# comms_sys_schematic_V1.net
KiCad netlist of a schematic drawn in EAGLE
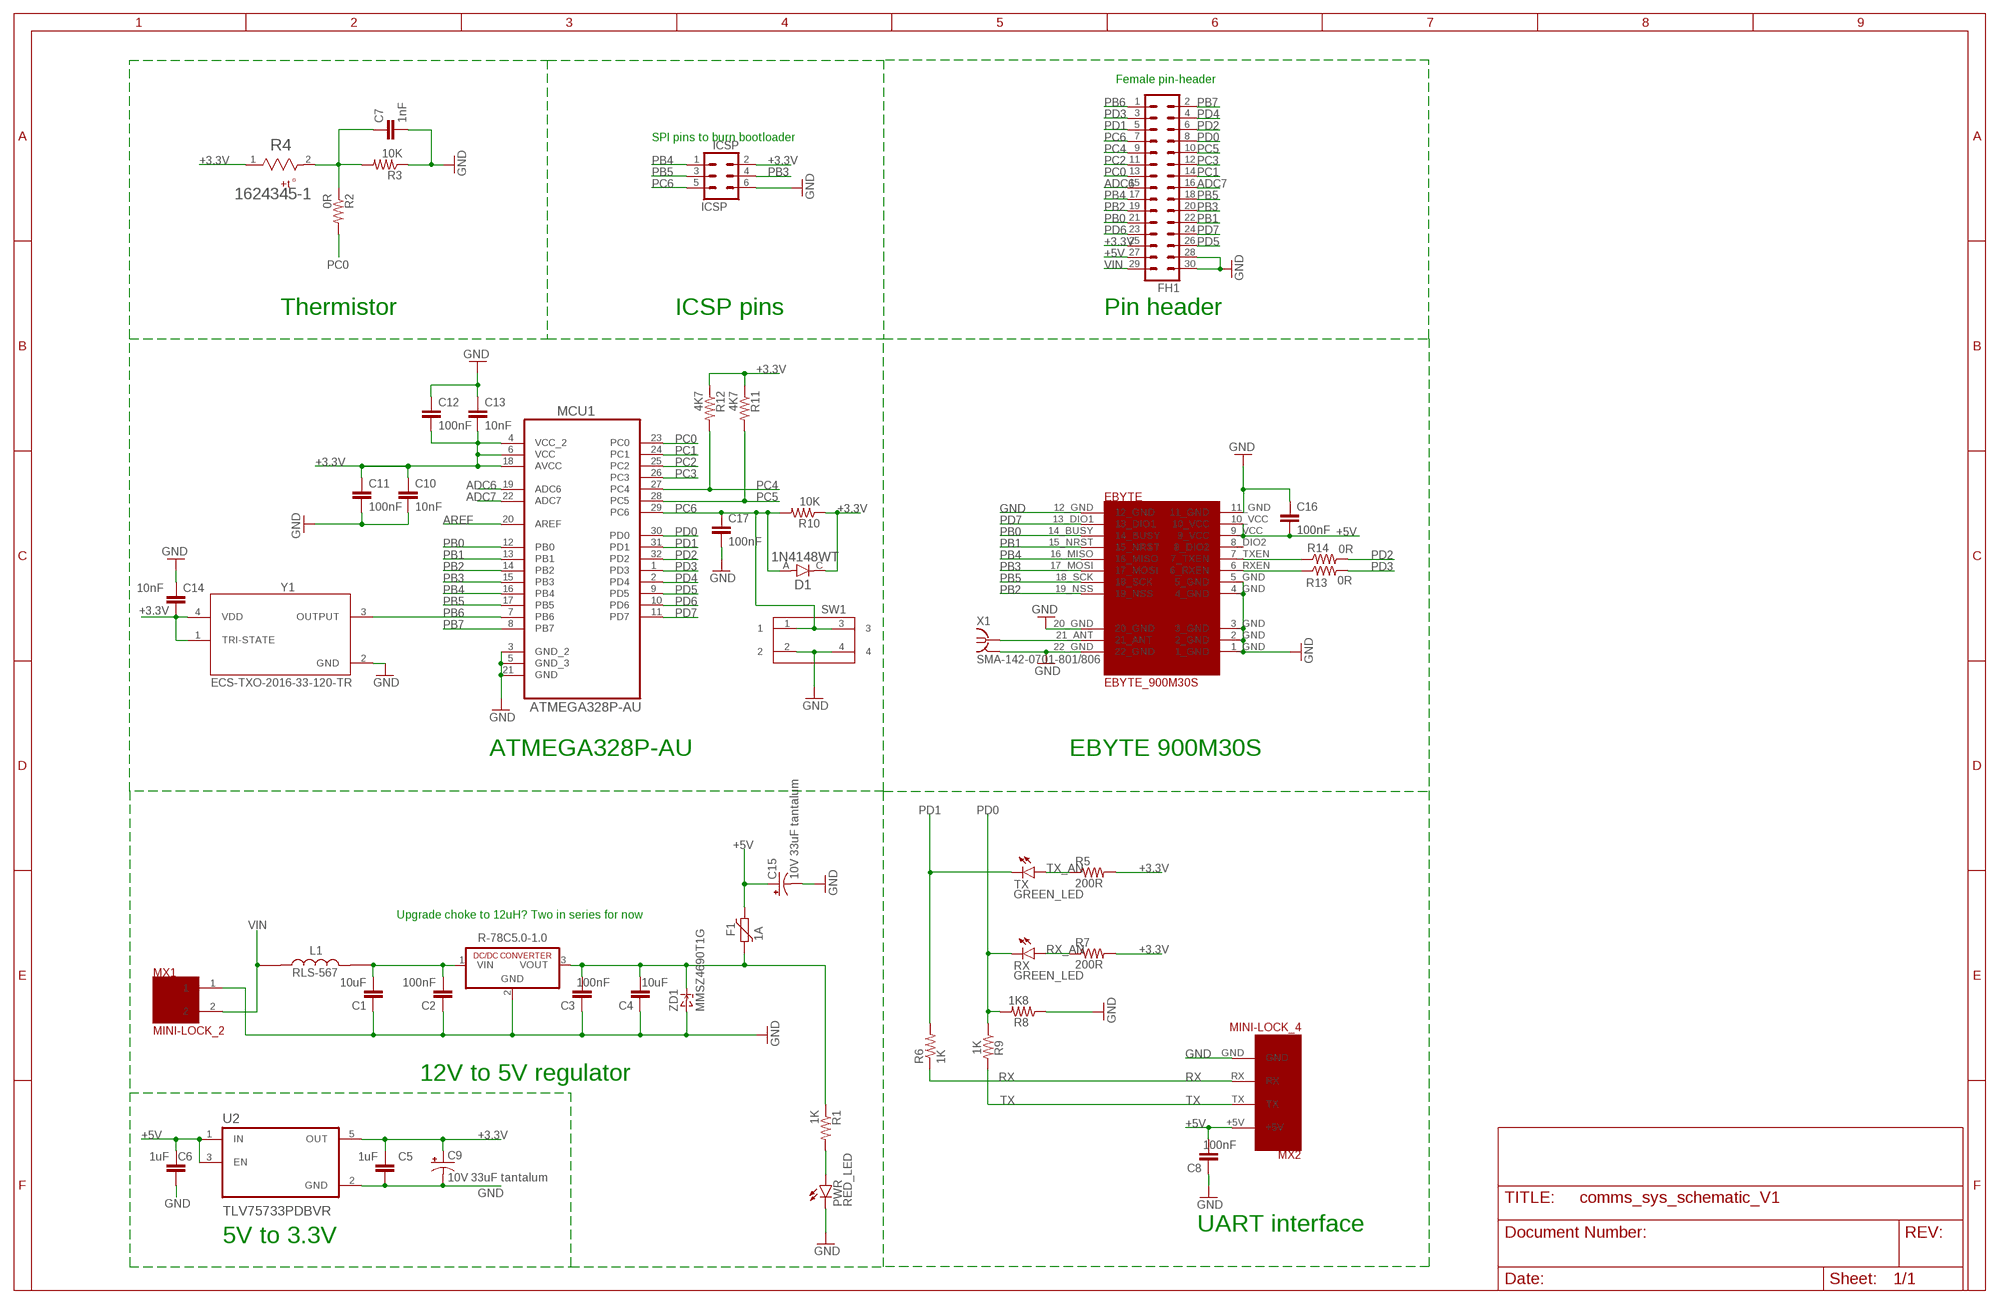
[diagram p0: schematic, sheet 1]

(export (version "E")
  (design (tool "Eeschema 10.0.6"))
  (components
    (comp (ref "C1")
      (value "10uF")
      (footprint "eagle-import:C0805")
      (libsource (lib "eagle-import") (part "C-EUC0805"))
    )
    (comp (ref "C2")
      (value "100nF")
      (footprint "eagle-import:C0805")
      (libsource (lib "eagle-import") (part "C-EUC0805"))
    )
    (comp (ref "C3")
      (value "100nF")
      (footprint "eagle-import:C0805")
      (libsource (lib "eagle-import") (part "C-EUC0805"))
    )
    (comp (ref "C4")
      (value "10uF")
      (footprint "eagle-import:C0805")
      (libsource (lib "eagle-import") (part "C-EUC0805"))
    )
    (comp (ref "C5")
      (value "1uF")
      (footprint "eagle-import:C0805")
      (libsource (lib "eagle-import") (part "C-EUC0805"))
    )
    (comp (ref "C6")
      (value "1uF")
      (footprint "eagle-import:C0805")
      (libsource (lib "eagle-import") (part "C-EUC0805"))
    )
    (comp (ref "C7")
      (value "1nF")
      (footprint "eagle-import:C0805")
      (libsource (lib "eagle-import") (part "C-EUC0805"))
    )
    (comp (ref "C8")
      (value "100nF")
      (footprint "eagle-import:C0805")
      (libsource (lib "eagle-import") (part "C-EUC0805"))
    )
    (comp (ref "C9")
      (value "10V 33uF tantalum")
      (footprint "eagle-import:CT3216")
      (libsource (lib "eagle-import") (part "CPOL-USCT3216"))
    )
    (comp (ref "C10")
      (value "10nF")
      (footprint "eagle-import:C0805")
      (libsource (lib "eagle-import") (part "C-EUC0805"))
    )
    (comp (ref "C11")
      (value "100nF")
      (footprint "eagle-import:C0805")
      (libsource (lib "eagle-import") (part "C-EUC0805"))
    )
    (comp (ref "C12")
      (value "100nF")
      (footprint "eagle-import:C0805")
      (libsource (lib "eagle-import") (part "C-EUC0805"))
    )
    (comp (ref "C13")
      (value "10nF")
      (footprint "eagle-import:C0805")
      (libsource (lib "eagle-import") (part "C-EUC0805"))
    )
    (comp (ref "C14")
      (value "10nF")
      (footprint "eagle-import:C0805")
      (libsource (lib "eagle-import") (part "C-EUC0805"))
    )
    (comp (ref "C15")
      (value "10V 33uF tantalum")
      (footprint "eagle-import:CT3216")
      (libsource (lib "eagle-import") (part "CPOL-USCT3216"))
    )
    (comp (ref "C16")
      (value "100nF")
      (footprint "eagle-import:C0805")
      (libsource (lib "eagle-import") (part "C-EUC0805"))
    )
    (comp (ref "C17")
      (value "100nF")
      (footprint "eagle-import:C0805")
      (libsource (lib "eagle-import") (part "C-EUC0805"))
    )
    (comp (ref "D1")
      (value "1N4148WT")
      (footprint "eagle-import:SODFL1608X70N")
      (fields (field (name "DIGI-KEY_PART_NUMBER") "1N4148WTCT-ND") (field (name "MF") "ON Semiconductor"))
      (libsource (lib "eagle-import") (part "1N4148WT"))
    )
    (comp (ref "EBYTE")
      (value "EBYTE_900M30S")
      (footprint "eagle-import:EBYTE_SX1262_900M30S_FOOTPRINT")
      (libsource (lib "eagle-import") (part "EBYTE_SX1262_900M30S"))
    )
    (comp (ref "F1")
      (value "1A")
      (footprint "eagle-import:PTC0805")
      (libsource (lib "eagle-import") (part "FUSE_PTC-0805"))
    )
    (comp (ref "FH1")
      (value "MA15-2")
      (footprint "eagle-import:MA15-2")
      (libsource (lib "eagle-import") (part "MA15-2"))
    )
    (comp (ref "ICSP")
      (value "ICSP")
      (footprint "eagle-import:MA03-2")
      (libsource (lib "eagle-import") (part "MA03-2"))
    )
    (comp (ref "L1")
      (value "RLS-567")
      (footprint "eagle-import:IND_RLS-567")
      (fields (field (name "MF") "Recom Power"))
      (libsource (lib "eagle-import") (part "RLS-567"))
    )
    (comp (ref "MCU1")
      (value "ATMEGA328P-AU")
      (footprint "eagle-import:QFP80P900X900X120-32N")
      (libsource (lib "eagle-import") (part "ATMEGA328P-AU"))
    )
    (comp (ref "MX1")
      (value "MINI-LOCK_2")
      (footprint "eagle-import:MINI-LOCK_2")
      (libsource (lib "eagle-import") (part "MINI-LOCK_2"))
    )
    (comp (ref "MX2")
      (value "MINI-LOCK_4")
      (footprint "eagle-import:MINI-LOCK_4")
      (libsource (lib "eagle-import") (part "MINI-LOCK_4"))
    )
    (comp (ref "PWR")
      (value "RED_LED")
      (footprint "eagle-import:CHIP-LED0805")
      (libsource (lib "eagle-import") (part "LEDCHIP-LED0805"))
    )
    (comp (ref "R1")
      (value "1K")
      (footprint "eagle-import:R0805")
      (libsource (lib "eagle-import") (part "R-US_R0805"))
    )
    (comp (ref "R2")
      (value "0R")
      (footprint "eagle-import:R0805")
      (libsource (lib "eagle-import") (part "R-US_R0805"))
    )
    (comp (ref "R3")
      (value "10K")
      (footprint "eagle-import:R0805")
      (libsource (lib "eagle-import") (part "R-US_R0805"))
    )
    (comp (ref "R4")
      (value "1624345-1")
      (footprint "eagle-import:THRMC2012X50N")
      (fields
        (field (name "DIGI-KEY_PART_NUMBER") "A106104CT-ND")
        (field (name "MF") "TE Connectivity")
        (field (name "MP") "NTC0805J10K")
      )
      (libsource (lib "eagle-import") (part "1624345-1"))
    )
    (comp (ref "R5")
      (value "200R")
      (footprint "eagle-import:R0805")
      (libsource (lib "eagle-import") (part "R-US_R0805"))
    )
    (comp (ref "R6")
      (value "1K")
      (footprint "eagle-import:R0805")
      (libsource (lib "eagle-import") (part "R-US_R0805"))
    )
    (comp (ref "R7")
      (value "200R")
      (footprint "eagle-import:R0805")
      (libsource (lib "eagle-import") (part "R-US_R0805"))
    )
    (comp (ref "R8")
      (value "1K8")
      (footprint "eagle-import:R0805")
      (libsource (lib "eagle-import") (part "R-US_R0805"))
    )
    (comp (ref "R9")
      (value "1K")
      (footprint "eagle-import:R0805")
      (libsource (lib "eagle-import") (part "R-US_R0805"))
    )
    (comp (ref "R10")
      (value "10K")
      (footprint "eagle-import:R0805")
      (libsource (lib "eagle-import") (part "R-US_R0805"))
    )
    (comp (ref "R11")
      (value "4K7")
      (footprint "eagle-import:R0805")
      (libsource (lib "eagle-import") (part "R-US_R0805"))
    )
    (comp (ref "R12")
      (value "4K7")
      (footprint "eagle-import:R0805")
      (libsource (lib "eagle-import") (part "R-US_R0805"))
    )
    (comp (ref "R13")
      (value "0R")
      (footprint "eagle-import:R0805")
      (libsource (lib "eagle-import") (part "R-US_R0805"))
    )
    (comp (ref "R14")
      (value "0R")
      (footprint "eagle-import:R0805")
      (libsource (lib "eagle-import") (part "R-US_R0805"))
    )
    (comp (ref "RX")
      (value "GREEN_LED")
      (footprint "eagle-import:CHIP-LED0805")
      (libsource (lib "eagle-import") (part "LEDCHIP-LED0805"))
    )
    (comp (ref "SW1")
      (value "430152043826")
      (footprint "eagle-import:430152043826")
      (libsource (lib "eagle-import") (part "430152043826"))
    )
    (comp (ref "TX")
      (value "GREEN_LED")
      (footprint "eagle-import:CHIP-LED0805")
      (libsource (lib "eagle-import") (part "LEDCHIP-LED0805"))
    )
    (comp (ref "U1")
      (value "R-78C5.0-1.0")
      (footprint "eagle-import:SIP3")
      (libsource (lib "eagle-import") (part "R-78C-1.05.0"))
    )
    (comp (ref "U2")
      (value "TLV75733PDBVR")
      (footprint "eagle-import:SOT95P280X145-5N")
      (fields (field (name "DIGI-KEY_PART_NUMBER") "296-50414-1-ND") (field (name "MF") "Texas Instruments"))
      (libsource (lib "eagle-import") (part "TLV75733PDBVR"))
    )
    (comp (ref "X1")
      (value "SMA-142-0701-801/806")
      (footprint "eagle-import:J502-ND-142-0701-801_806")
      (fields (field (name "MF") "JOHNSON COMPONENTS") (field (name "MPN") "142-0701-801"))
      (libsource (lib "eagle-import") (part "SMA-142-0701-801/806"))
    )
    (comp (ref "Y1")
      (value "ECS-TXO-2016-33-120-TR")
      (footprint "eagle-import:OSC_ECS-TXO-2016-33-120-TR")
      (fields (field (name "DIGI-KEY_PART_NUMBER") "XC3160CT-ND") (field (name "MF") "ECS Inc."))
      (libsource (lib "eagle-import") (part "ECS-TXO-2016-33-120-TR"))
    )
    (comp (ref "ZD1")
      (value "MMSZ4690T1G")
      (footprint "eagle-import:SOD-123")
      (libsource (lib "eagle-import") (part "ZENERSOD-123"))
    )
  )
  (nets
    (net (code "1") (name "/+3.3V") (class "Default")
      (node (ref "C10") (pin "1") (pinfunction "1_1") (pintype "passive"))
      (node (ref "C11") (pin "1") (pinfunction "1_1") (pintype "passive"))
      (node (ref "C12") (pin "2") (pinfunction "2_2") (pintype "passive"))
      (node (ref "C13") (pin "2") (pinfunction "2_2") (pintype "passive"))
      (node (ref "C14") (pin "2") (pinfunction "2_2") (pintype "passive"))
      (node (ref "C5") (pin "2") (pinfunction "2_2") (pintype "passive"))
      (node (ref "C9") (pin "+") (pinfunction "+_+") (pintype "passive"))
      (node (ref "D1") (pin "C") (pinfunction "C_C") (pintype "passive"))
      (node (ref "FH1") (pin "25") (pinfunction "29_25") (pintype "passive"))
      (node (ref "ICSP") (pin "2") (pinfunction "2_2") (pintype "passive"))
      (node (ref "MCU1") (pin "18") (pinfunction "AVCC_18") (pintype "power_in"))
      (node (ref "MCU1") (pin "4") (pinfunction "VCC_2_4") (pintype "power_in"))
      (node (ref "MCU1") (pin "6") (pinfunction "VCC_6") (pintype "power_in"))
      (node (ref "R10") (pin "1") (pinfunction "1_1") (pintype "passive"))
      (node (ref "R11") (pin "1") (pinfunction "1_1") (pintype "passive"))
      (node (ref "R12") (pin "1") (pinfunction "1_1") (pintype "passive"))
      (node (ref "R4") (pin "1") (pinfunction "1_1") (pintype "passive"))
      (node (ref "R5") (pin "2") (pinfunction "2_2") (pintype "passive"))
      (node (ref "R7") (pin "2") (pinfunction "2_2") (pintype "passive"))
      (node (ref "U2") (pin "5") (pinfunction "OUT_5") (pintype "output"))
      (node (ref "Y1") (pin "1") (pinfunction "TRI-STATE_1") (pintype "input"))
      (node (ref "Y1") (pin "4") (pinfunction "VDD_4") (pintype "input"))
    )
    (net (code "2") (name "/+5V") (class "Default")
      (node (ref "C15") (pin "+") (pinfunction "+_+") (pintype "passive"))
      (node (ref "C16") (pin "2") (pinfunction "2_2") (pintype "passive"))
      (node (ref "C6") (pin "2") (pinfunction "2_2") (pintype "passive"))
      (node (ref "C8") (pin "2") (pinfunction "2_2") (pintype "passive"))
      (node (ref "EBYTE") (pin "10_VCC") (pinfunction "10_VCC_10_VCC") (pintype "power_in"))
      (node (ref "EBYTE") (pin "9_VCC") (pinfunction "9_VCC_9_VCC") (pintype "power_in"))
      (node (ref "F1") (pin "2") (pinfunction "2_2") (pintype "passive"))
      (node (ref "FH1") (pin "27") (pinfunction "31_27") (pintype "passive"))
      (node (ref "MX2") (pin "+5V") (pinfunction "+5V_+5V") (pintype "bidirectional"))
      (node (ref "U2") (pin "1") (pinfunction "IN_1") (pintype "input"))
      (node (ref "U2") (pin "3") (pinfunction "EN_3") (pintype "bidirectional"))
    )
    (net (code "3") (name "/ADC6") (class "Default")
      (node (ref "FH1") (pin "15") (pinfunction "19_15") (pintype "passive"))
      (node (ref "MCU1") (pin "19") (pinfunction "ADC6_19") (pintype "input"))
    )
    (net (code "4") (name "/ADC7") (class "Default")
      (node (ref "FH1") (pin "16") (pinfunction "20_16") (pintype "passive"))
      (node (ref "MCU1") (pin "22") (pinfunction "ADC7_22") (pintype "input"))
    )
    (net (code "5") (name "/AREF") (class "Default")
      (node (ref "MCU1") (pin "20") (pinfunction "AREF_20") (pintype "input"))
    )
    (net (code "6") (name "/PB0") (class "Default")
      (node (ref "EBYTE") (pin "14_BUSY") (pinfunction "14_BUSY_14_BUSY") (pintype "bidirectional"))
      (node (ref "FH1") (pin "21") (pinfunction "25_21") (pintype "passive"))
      (node (ref "MCU1") (pin "12") (pinfunction "PB0_12") (pintype "bidirectional"))
    )
    (net (code "7") (name "/PB1") (class "Default")
      (node (ref "EBYTE") (pin "15_NRST") (pinfunction "15_NRST_15_NRST") (pintype "bidirectional"))
      (node (ref "FH1") (pin "22") (pinfunction "26_22") (pintype "passive"))
      (node (ref "MCU1") (pin "13") (pinfunction "PB1_13") (pintype "bidirectional"))
    )
    (net (code "8") (name "/PB2") (class "Default")
      (node (ref "EBYTE") (pin "19_NSS") (pinfunction "19_NSS_19_NSS") (pintype "bidirectional"))
      (node (ref "FH1") (pin "19") (pinfunction "23_19") (pintype "passive"))
      (node (ref "MCU1") (pin "14") (pinfunction "PB2_14") (pintype "bidirectional"))
    )
    (net (code "9") (name "/PB3") (class "Default")
      (node (ref "EBYTE") (pin "17_MOSI") (pinfunction "17_MOSI_17_MOSI") (pintype "bidirectional"))
      (node (ref "FH1") (pin "20") (pinfunction "24_20") (pintype "passive"))
      (node (ref "ICSP") (pin "4") (pinfunction "4_4") (pintype "passive"))
      (node (ref "MCU1") (pin "15") (pinfunction "PB3_15") (pintype "bidirectional"))
    )
    (net (code "10") (name "/PB4") (class "Default")
      (node (ref "EBYTE") (pin "16_MISO") (pinfunction "16_MISO_16_MISO") (pintype "bidirectional"))
      (node (ref "FH1") (pin "17") (pinfunction "21_17") (pintype "passive"))
      (node (ref "ICSP") (pin "1") (pinfunction "1_1") (pintype "passive"))
      (node (ref "MCU1") (pin "16") (pinfunction "PB4_16") (pintype "bidirectional"))
    )
    (net (code "11") (name "/PB5") (class "Default")
      (node (ref "EBYTE") (pin "18_SCK") (pinfunction "18_SCK_18_SCK") (pintype "bidirectional"))
      (node (ref "FH1") (pin "18") (pinfunction "22_18") (pintype "passive"))
      (node (ref "ICSP") (pin "3") (pinfunction "3_3") (pintype "passive"))
      (node (ref "MCU1") (pin "17") (pinfunction "PB5_17") (pintype "bidirectional"))
    )
    (net (code "12") (name "/PB6") (class "Default")
      (node (ref "FH1") (pin "1") (pinfunction "5_1") (pintype "passive"))
      (node (ref "MCU1") (pin "7") (pinfunction "PB6_7") (pintype "bidirectional"))
      (node (ref "Y1") (pin "3") (pinfunction "OUTPUT_3") (pintype "output"))
    )
    (net (code "13") (name "/PB7") (class "Default")
      (node (ref "FH1") (pin "2") (pinfunction "6_2") (pintype "passive"))
      (node (ref "MCU1") (pin "8") (pinfunction "PB7_8") (pintype "bidirectional"))
    )
    (net (code "14") (name "/PC0") (class "Default")
      (node (ref "FH1") (pin "13") (pinfunction "17_13") (pintype "passive"))
      (node (ref "MCU1") (pin "23") (pinfunction "PC0_23") (pintype "bidirectional"))
      (node (ref "R2") (pin "2") (pinfunction "2_2") (pintype "passive"))
    )
    (net (code "15") (name "/PC1") (class "Default")
      (node (ref "FH1") (pin "14") (pinfunction "18_14") (pintype "passive"))
      (node (ref "MCU1") (pin "24") (pinfunction "PC1_24") (pintype "bidirectional"))
    )
    (net (code "16") (name "/PC2") (class "Default")
      (node (ref "FH1") (pin "11") (pinfunction "15_11") (pintype "passive"))
      (node (ref "MCU1") (pin "25") (pinfunction "PC2_25") (pintype "bidirectional"))
    )
    (net (code "17") (name "/PC3") (class "Default")
      (node (ref "FH1") (pin "12") (pinfunction "16_12") (pintype "passive"))
      (node (ref "MCU1") (pin "26") (pinfunction "PC3_26") (pintype "bidirectional"))
    )
    (net (code "18") (name "/PC4") (class "Default")
      (node (ref "FH1") (pin "9") (pinfunction "13_9") (pintype "passive"))
      (node (ref "MCU1") (pin "27") (pinfunction "PC4_27") (pintype "bidirectional"))
      (node (ref "R12") (pin "2") (pinfunction "2_2") (pintype "passive"))
    )
    (net (code "19") (name "/PC5") (class "Default")
      (node (ref "FH1") (pin "10") (pinfunction "14_10") (pintype "passive"))
      (node (ref "MCU1") (pin "28") (pinfunction "PC5_28") (pintype "bidirectional"))
      (node (ref "R11") (pin "2") (pinfunction "2_2") (pintype "passive"))
    )
    (net (code "20") (name "/PC6") (class "Default")
      (node (ref "C17") (pin "1") (pinfunction "1_1") (pintype "passive"))
      (node (ref "D1") (pin "A") (pinfunction "A_A") (pintype "passive"))
      (node (ref "FH1") (pin "7") (pinfunction "11_7") (pintype "passive"))
      (node (ref "ICSP") (pin "5") (pinfunction "5_5") (pintype "passive"))
      (node (ref "MCU1") (pin "29") (pinfunction "PC6_29") (pintype "bidirectional"))
      (node (ref "R10") (pin "2") (pinfunction "2_2") (pintype "passive"))
      (node (ref "SW1") (pin "1") (pinfunction "1_1") (pintype "bidirectional"))
      (node (ref "SW1") (pin "3") (pinfunction "3_3") (pintype "bidirectional"))
    )
    (net (code "21") (name "/PD0") (class "Default")
      (node (ref "FH1") (pin "8") (pinfunction "12_8") (pintype "passive"))
      (node (ref "MCU1") (pin "30") (pinfunction "PD0_30") (pintype "bidirectional"))
      (node (ref "R8") (pin "2") (pinfunction "2_2") (pintype "passive"))
      (node (ref "R9") (pin "1") (pinfunction "1_1") (pintype "passive"))
      (node (ref "RX") (pin "C") (pinfunction "C_C") (pintype "passive"))
    )
    (net (code "22") (name "/PD1") (class "Default")
      (node (ref "FH1") (pin "5") (pinfunction "9_5") (pintype "passive"))
      (node (ref "MCU1") (pin "31") (pinfunction "PD1_31") (pintype "bidirectional"))
      (node (ref "R6") (pin "2") (pinfunction "2_2") (pintype "passive"))
      (node (ref "TX") (pin "C") (pinfunction "C_C") (pintype "passive"))
    )
    (net (code "23") (name "/PD2") (class "Default")
      (node (ref "FH1") (pin "6") (pinfunction "10_6") (pintype "passive"))
      (node (ref "MCU1") (pin "32") (pinfunction "PD2_32") (pintype "bidirectional"))
      (node (ref "R14") (pin "2") (pinfunction "2_2") (pintype "passive"))
    )
    (net (code "24") (name "/PD3") (class "Default")
      (node (ref "FH1") (pin "3") (pinfunction "7_3") (pintype "passive"))
      (node (ref "MCU1") (pin "1") (pinfunction "PD3_1") (pintype "bidirectional"))
      (node (ref "R13") (pin "2") (pinfunction "2_2") (pintype "passive"))
    )
    (net (code "25") (name "/PD4") (class "Default")
      (node (ref "FH1") (pin "4") (pinfunction "8_4") (pintype "passive"))
      (node (ref "MCU1") (pin "2") (pinfunction "PD4_2") (pintype "bidirectional"))
    )
    (net (code "26") (name "/PD5") (class "Default")
      (node (ref "FH1") (pin "26") (pinfunction "30_26") (pintype "passive"))
      (node (ref "MCU1") (pin "9") (pinfunction "PD5_9") (pintype "bidirectional"))
    )
    (net (code "27") (name "/PD6") (class "Default")
      (node (ref "FH1") (pin "23") (pinfunction "27_23") (pintype "passive"))
      (node (ref "MCU1") (pin "10") (pinfunction "PD6_10") (pintype "bidirectional"))
    )
    (net (code "28") (name "/PD7") (class "Default")
      (node (ref "EBYTE") (pin "13_DIO1") (pinfunction "13_DIO1_13_DIO1") (pintype "bidirectional"))
      (node (ref "FH1") (pin "24") (pinfunction "28_24") (pintype "passive"))
      (node (ref "MCU1") (pin "11") (pinfunction "PD7_11") (pintype "bidirectional"))
    )
    (net (code "29") (name "/RX") (class "Default")
      (node (ref "MX2") (pin "RX") (pinfunction "RX_RX") (pintype "bidirectional"))
      (node (ref "R6") (pin "1") (pinfunction "1_1") (pintype "passive"))
    )
    (net (code "30") (name "/RX_AN") (class "Default")
      (node (ref "R7") (pin "1") (pinfunction "1_1") (pintype "passive"))
      (node (ref "RX") (pin "A") (pinfunction "A_A") (pintype "passive"))
    )
    (net (code "31") (name "/TX") (class "Default")
      (node (ref "MX2") (pin "TX") (pinfunction "TX_TX") (pintype "bidirectional"))
      (node (ref "R9") (pin "2") (pinfunction "2_2") (pintype "passive"))
    )
    (net (code "32") (name "/TX_AN") (class "Default")
      (node (ref "R5") (pin "1") (pinfunction "1_1") (pintype "passive"))
      (node (ref "TX") (pin "A") (pinfunction "A_A") (pintype "passive"))
    )
    (net (code "33") (name "/VIN") (class "Default")
      (node (ref "FH1") (pin "29") (pinfunction "33_29") (pintype "passive"))
      (node (ref "L1") (pin "1") (pinfunction "1_1") (pintype "passive"))
      (node (ref "MX1") (pin "2") (pinfunction "2_2") (pintype "bidirectional"))
    )
    (net (code "34") (name "GND") (class "Default")
      (node (ref "C1") (pin "1") (pinfunction "1_1") (pintype "passive"))
      (node (ref "C10") (pin "2") (pinfunction "2_2") (pintype "passive"))
      (node (ref "C11") (pin "2") (pinfunction "2_2") (pintype "passive"))
      (node (ref "C12") (pin "1") (pinfunction "1_1") (pintype "passive"))
      (node (ref "C13") (pin "1") (pinfunction "1_1") (pintype "passive"))
      (node (ref "C14") (pin "1") (pinfunction "1_1") (pintype "passive"))
      (node (ref "C15") (pin "-") (pinfunction "-_-") (pintype "passive"))
      (node (ref "C16") (pin "1") (pinfunction "1_1") (pintype "passive"))
      (node (ref "C17") (pin "2") (pinfunction "2_2") (pintype "passive"))
      (node (ref "C2") (pin "1") (pinfunction "1_1") (pintype "passive"))
      (node (ref "C3") (pin "1") (pinfunction "1_1") (pintype "passive"))
      (node (ref "C4") (pin "1") (pinfunction "1_1") (pintype "passive"))
      (node (ref "C5") (pin "1") (pinfunction "1_1") (pintype "passive"))
      (node (ref "C6") (pin "1") (pinfunction "1_1") (pintype "passive"))
      (node (ref "C7") (pin "2") (pinfunction "2_2") (pintype "passive"))
      (node (ref "C8") (pin "1") (pinfunction "1_1") (pintype "passive"))
      (node (ref "C9") (pin "-") (pinfunction "-_-") (pintype "passive"))
      (node (ref "EBYTE") (pin "11_GND") (pinfunction "11_GND_11_GND") (pintype "power_in"))
      (node (ref "EBYTE") (pin "12_GND") (pinfunction "12_GND_12_GND") (pintype "power_in"))
      (node (ref "EBYTE") (pin "1_GND") (pinfunction "1_GND_1_GND") (pintype "power_in"))
      (node (ref "EBYTE") (pin "20_GND") (pinfunction "20_GND_20_GND") (pintype "power_in"))
      (node (ref "EBYTE") (pin "22_GND") (pinfunction "22_GND_22_GND") (pintype "power_in"))
      (node (ref "EBYTE") (pin "2_GND") (pinfunction "2_GND_2_GND") (pintype "power_in"))
      (node (ref "EBYTE") (pin "3_GND") (pinfunction "3_GND_3_GND") (pintype "power_in"))
      (node (ref "EBYTE") (pin "4_GND") (pinfunction "4_GND_4_GND") (pintype "power_in"))
      (node (ref "EBYTE") (pin "5_GND") (pinfunction "5_GND_5_GND") (pintype "power_in"))
      (node (ref "FH1") (pin "28") (pinfunction "32_28") (pintype "passive"))
      (node (ref "FH1") (pin "30") (pinfunction "34_30") (pintype "passive"))
      (node (ref "ICSP") (pin "6") (pinfunction "6_6") (pintype "passive"))
      (node (ref "MCU1") (pin "21") (pinfunction "GND_21") (pintype "passive"))
      (node (ref "MCU1") (pin "3") (pinfunction "GND_2_3") (pintype "passive"))
      (node (ref "MCU1") (pin "5") (pinfunction "GND_3_5") (pintype "passive"))
      (node (ref "MX1") (pin "1") (pinfunction "1_1") (pintype "bidirectional"))
      (node (ref "MX2") (pin "GND") (pinfunction "GND_GND") (pintype "bidirectional"))
      (node (ref "PWR") (pin "C") (pinfunction "C_C") (pintype "passive"))
      (node (ref "R3") (pin "1") (pinfunction "1_1") (pintype "passive"))
      (node (ref "R8") (pin "1") (pinfunction "1_1") (pintype "passive"))
      (node (ref "SW1") (pin "2") (pinfunction "2_2") (pintype "bidirectional"))
      (node (ref "SW1") (pin "4") (pinfunction "4_4") (pintype "bidirectional"))
      (node (ref "U1") (pin "2") (pinfunction "GND_2") (pintype "passive"))
      (node (ref "U2") (pin "2") (pinfunction "GND_2") (pintype "power_in"))
      (node (ref "X1") (pin "G@1") (pinfunction "2_G@1") (pintype "passive"))
      (node (ref "X1") (pin "G@2") (pinfunction "2_G@2") (pintype "passive"))
      (node (ref "X1") (pin "G@3") (pinfunction "2_G@3") (pintype "passive"))
      (node (ref "X1") (pin "G@4") (pinfunction "2_G@4") (pintype "passive"))
      (node (ref "Y1") (pin "2") (pinfunction "GND_2") (pintype "power_in"))
      (node (ref "ZD1") (pin "A") (pinfunction "A_A") (pintype "passive"))
    )
    (net (code "35") (name "Net-(C7-Pad1)") (class "Default")
      (node (ref "C7") (pin "1") (pinfunction "1_1") (pintype "passive"))
      (node (ref "R2") (pin "1") (pinfunction "1_1") (pintype "passive"))
      (node (ref "R3") (pin "2") (pinfunction "2_2") (pintype "passive"))
      (node (ref "R4") (pin "2") (pinfunction "2_2") (pintype "passive"))
    )
    (net (code "36") (name "Net-(EBYTE-Pad6_RXEN)") (class "Default")
      (node (ref "EBYTE") (pin "6_RXEN") (pinfunction "6_RXEN_6_RXEN") (pintype "bidirectional"))
      (node (ref "R13") (pin "1") (pinfunction "1_1") (pintype "passive"))
    )
    (net (code "37") (name "Net-(EBYTE-Pad7_TXEN)") (class "Default")
      (node (ref "EBYTE") (pin "7_TXEN") (pinfunction "7_TXEN_7_TXEN") (pintype "bidirectional"))
      (node (ref "R14") (pin "1") (pinfunction "1_1") (pintype "passive"))
    )
    (net (code "38") (name "Net-(EBYTE-Pad21_ANT)") (class "Default")
      (node (ref "EBYTE") (pin "21_ANT") (pinfunction "21_ANT_21_ANT") (pintype "bidirectional"))
      (node (ref "X1") (pin "1") (pinfunction "1_1") (pintype "passive"))
    )
    (net (code "39") (name "Net-(PWR-PadA)") (class "Default")
      (node (ref "PWR") (pin "A") (pinfunction "A_A") (pintype "passive"))
      (node (ref "R1") (pin "2") (pinfunction "2_2") (pintype "passive"))
    )
    (net (code "40") (name "Net-(U1-VIN)") (class "Default")
      (node (ref "C1") (pin "2") (pinfunction "2_2") (pintype "passive"))
      (node (ref "C2") (pin "2") (pinfunction "2_2") (pintype "passive"))
      (node (ref "L1") (pin "2") (pinfunction "2_2") (pintype "passive"))
      (node (ref "U1") (pin "1") (pinfunction "VIN_1") (pintype "passive"))
    )
    (net (code "41") (name "Net-(U1-VOUT)") (class "Default")
      (node (ref "C3") (pin "2") (pinfunction "2_2") (pintype "passive"))
      (node (ref "C4") (pin "2") (pinfunction "2_2") (pintype "passive"))
      (node (ref "F1") (pin "1") (pinfunction "1_1") (pintype "passive"))
      (node (ref "R1") (pin "1") (pinfunction "1_1") (pintype "passive"))
      (node (ref "U1") (pin "3") (pinfunction "VOUT_3") (pintype "passive"))
      (node (ref "ZD1") (pin "C") (pinfunction "C_C") (pintype "passive"))
    )
    (net (code "42") (name "unconnected-(EBYTE-Pad8_DIO2)") (class "Default")
      (node (ref "EBYTE") (pin "8_DIO2") (pinfunction "8_DIO2_8_DIO2") (pintype "bidirectional"))
    )
  )
)
